# Laser_Tag_Dip_New.net
KiCad netlist of a schematic drawn in EAGLE
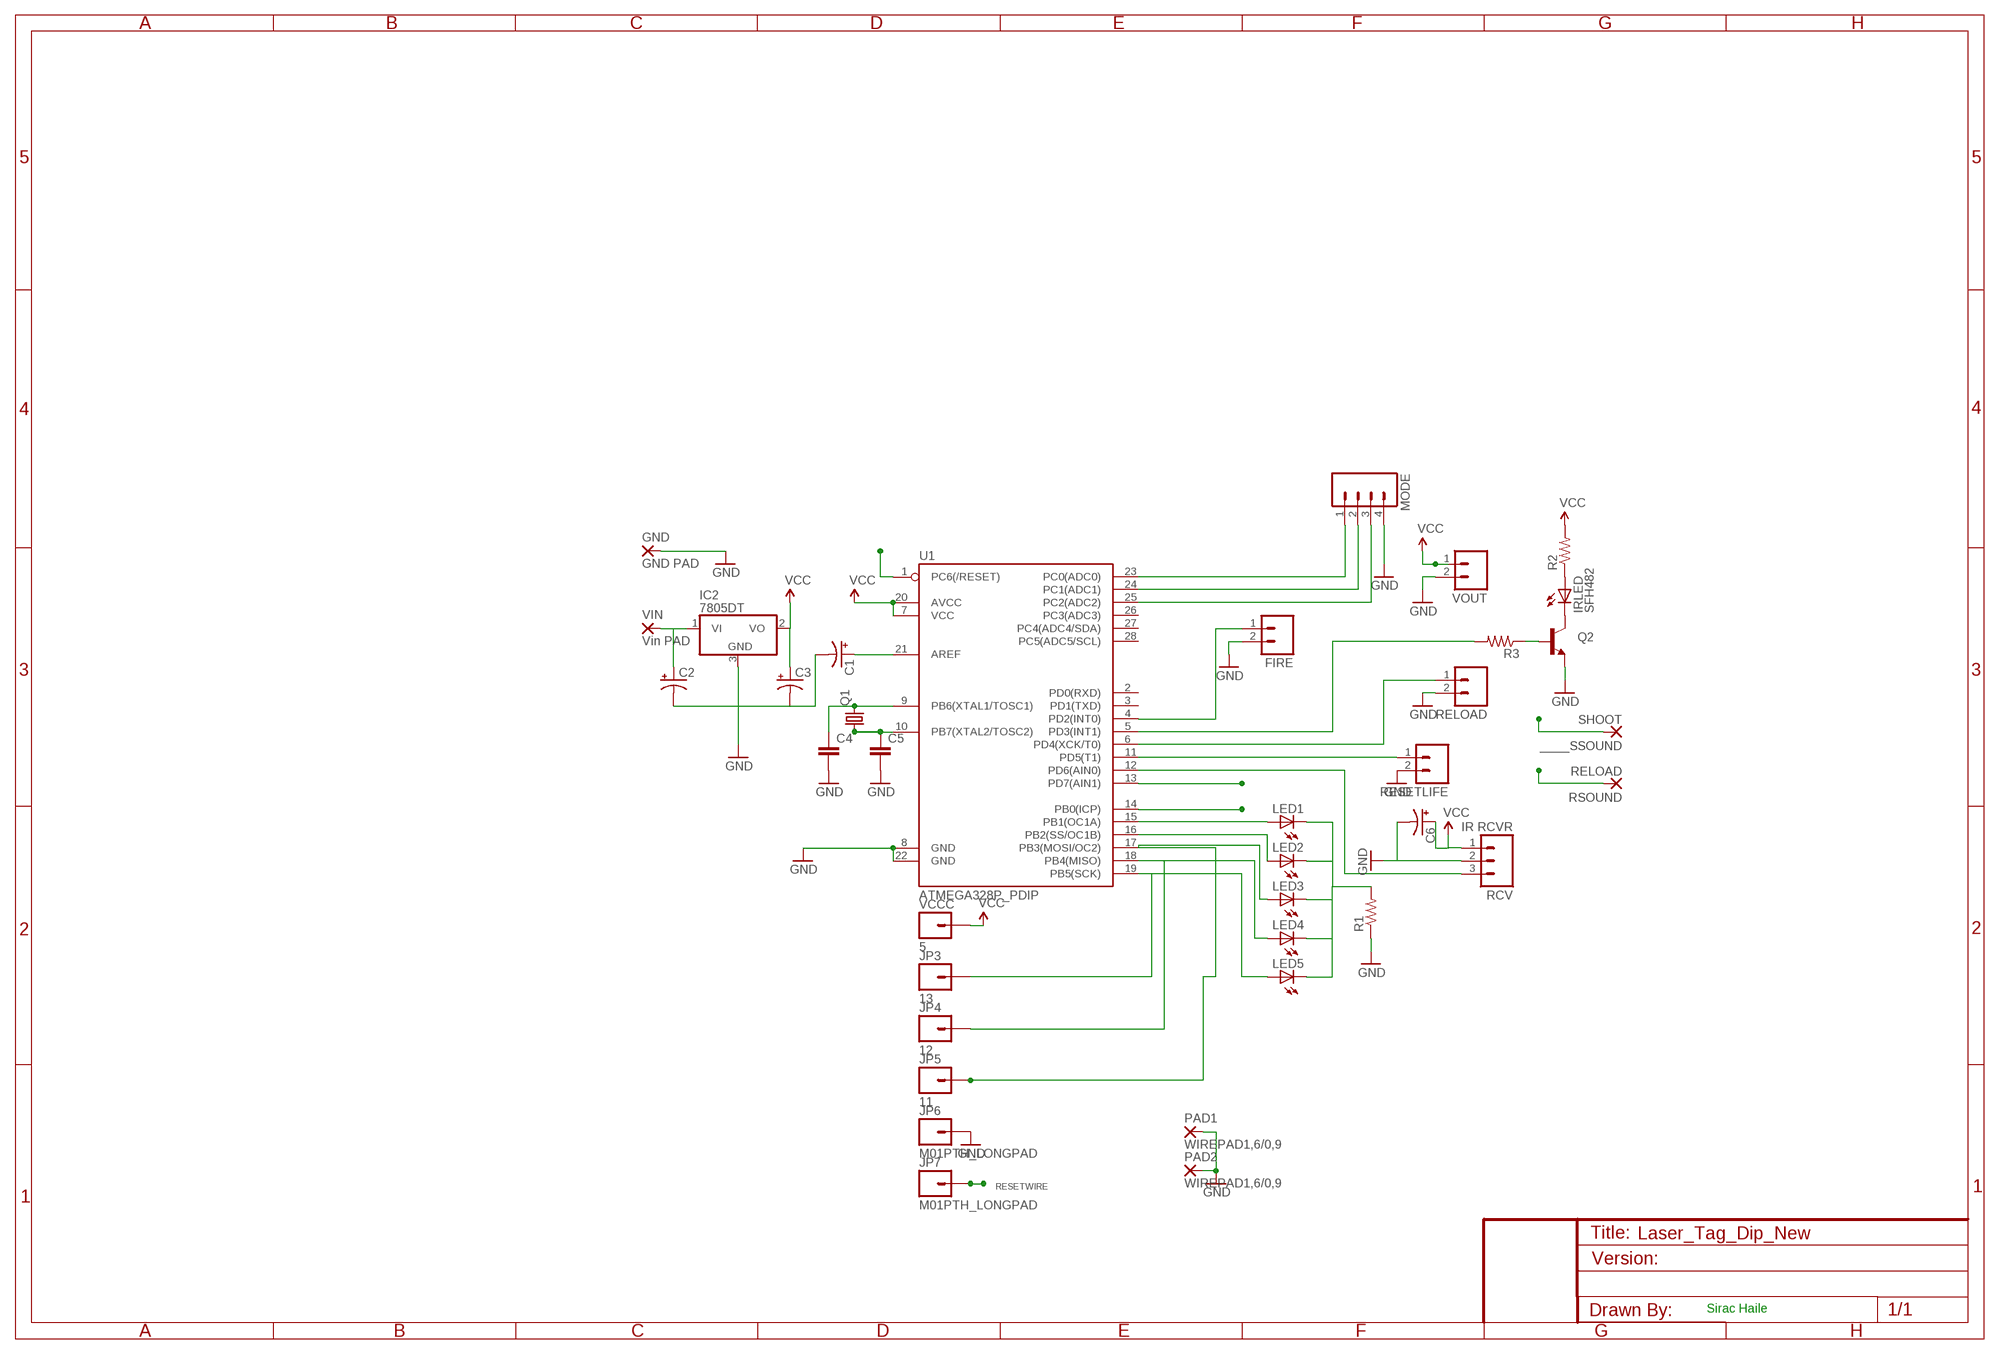
[diagram p0: schematic, sheet 1]

(export (version "E")
  (design (tool "Eeschema 10.0.6"))
  (components
    (comp (ref "C1")
      (value "CAP_POLPTH1")
      (footprint "eagle-import:CPOL-RADIAL-100UF-25V")
      (libsource (lib "eagle-import") (part "CAP_POLPTH1"))
    )
    (comp (ref "C2")
      (value "CAP_POLPTH1")
      (footprint "eagle-import:CPOL-RADIAL-100UF-25V")
      (libsource (lib "eagle-import") (part "CAP_POLPTH1"))
    )
    (comp (ref "C3")
      (value "CAP_POLPTH1")
      (footprint "eagle-import:CPOL-RADIAL-100UF-25V")
      (libsource (lib "eagle-import") (part "CAP_POLPTH1"))
    )
    (comp (ref "C4")
      (value "CAPEZ")
      (footprint "eagle-import:CAP-PTH-SMALLEZ")
      (libsource (lib "eagle-import") (part "CAPEZ"))
    )
    (comp (ref "C5")
      (value "CAPEZ")
      (footprint "eagle-import:CAP-PTH-SMALLEZ")
      (libsource (lib "eagle-import") (part "CAPEZ"))
    )
    (comp (ref "C6")
      (value "CAP_POLPTH1")
      (footprint "eagle-import:CPOL-RADIAL-100UF-25V")
      (libsource (lib "eagle-import") (part "CAP_POLPTH1"))
    )
    (comp (ref "FIRE")
      (value "M02LOCK_LONGPADS")
      (footprint "eagle-import:1X02_LOCK_LONGPADS")
      (libsource (lib "eagle-import") (part "M02LOCK_LONGPADS"))
    )
    (comp (ref "GND")
      (value "GND PAD")
      (footprint "eagle-import:2,54_1,1")
      (libsource (lib "eagle-import") (part "WIREPAD2,54/1,1"))
    )
    (comp (ref "IC2")
      (value "7805DT")
      (footprint "eagle-import:TO252")
      (libsource (lib "eagle-import") (part "78DT05"))
    )
    (comp (ref "IRLED")
      (value "SFH482")
      (footprint "eagle-import:SFH482")
      (libsource (lib "eagle-import") (part "SFH482"))
    )
    (comp (ref "JP3")
      (value "13")
      (footprint "eagle-import:1X01_LONGPAD")
      (libsource (lib "eagle-import") (part "M01PTH_LONGPAD"))
    )
    (comp (ref "JP4")
      (value "12")
      (footprint "eagle-import:1X01_LONGPAD")
      (libsource (lib "eagle-import") (part "M01PTH_LONGPAD"))
    )
    (comp (ref "JP5")
      (value "11")
      (footprint "eagle-import:1X01_LONGPAD")
      (libsource (lib "eagle-import") (part "M01PTH_LONGPAD"))
    )
    (comp (ref "JP6")
      (value "M01PTH_LONGPAD")
      (footprint "eagle-import:1X01_LONGPAD")
      (libsource (lib "eagle-import") (part "M01PTH_LONGPAD"))
    )
    (comp (ref "JP7")
      (value "M01PTH_LONGPAD")
      (footprint "eagle-import:1X01_LONGPAD")
      (libsource (lib "eagle-import") (part "M01PTH_LONGPAD"))
    )
    (comp (ref "LED1")
      (value "LED5MM")
      (footprint "eagle-import:LED5MM")
      (libsource (lib "eagle-import") (part "LED5MM"))
    )
    (comp (ref "LED2")
      (value "LED5MM")
      (footprint "eagle-import:LED5MM")
      (libsource (lib "eagle-import") (part "LED5MM"))
    )
    (comp (ref "LED3")
      (value "LED5MM")
      (footprint "eagle-import:LED5MM")
      (libsource (lib "eagle-import") (part "LED5MM"))
    )
    (comp (ref "LED4")
      (value "LED5MM")
      (footprint "eagle-import:LED5MM")
      (libsource (lib "eagle-import") (part "LED5MM"))
    )
    (comp (ref "LED5")
      (value "LED5MM")
      (footprint "eagle-import:LED5MM")
      (libsource (lib "eagle-import") (part "LED5MM"))
    )
    (comp (ref "MODE")
      (value "M04LONGPADS")
      (footprint "eagle-import:1X04_LONGPADS")
      (libsource (lib "eagle-import") (part "M04LONGPADS"))
    )
    (comp (ref "PAD1")
      (value "WIREPAD1,6/0,9")
      (footprint "eagle-import:1,6_0,9")
      (libsource (lib "eagle-import") (part "WIREPAD1,6/0,9"))
    )
    (comp (ref "PAD2")
      (value "WIREPAD1,6/0,9")
      (footprint "eagle-import:1,6_0,9")
      (libsource (lib "eagle-import") (part "WIREPAD1,6/0,9"))
    )
    (comp (ref "Q1")
      (value "CRYSTALHC49S")
      (footprint "eagle-import:HC49_S")
      (fields (field (name "OC_FARNELL") "1667008"))
      (libsource (lib "eagle-import") (part "CRYSTALHC49S"))
    )
    (comp (ref "Q2")
      (value "TRANSISTOR_NPNTO-92-AMMO")
      (footprint "eagle-import:TO-92-AMMO")
      (libsource (lib "eagle-import") (part "TRANSISTOR_NPNTO-92-AMMO"))
    )
    (comp (ref "R1")
      (value "RESISTORKIT")
      (footprint "eagle-import:AXIAL-0.3-KIT")
      (libsource (lib "eagle-import") (part "SparkFun-Resistors_RESISTORKIT"))
    )
    (comp (ref "R2")
      (value "RESISTORKIT")
      (footprint "eagle-import:AXIAL-0.3-KIT")
      (libsource (lib "eagle-import") (part "RESISTORKIT"))
    )
    (comp (ref "R3")
      (value "RESISTORKIT")
      (footprint "eagle-import:AXIAL-0.3-KIT")
      (libsource (lib "eagle-import") (part "RESISTORKIT"))
    )
    (comp (ref "RCV")
      (value "IR RCVR")
      (footprint "eagle-import:1X03")
      (libsource (lib "eagle-import") (part "M03PTH"))
    )
    (comp (ref "RELOAD")
      (value "M02LOCK_LONGPADS")
      (footprint "eagle-import:1X02_LOCK_LONGPADS")
      (libsource (lib "eagle-import") (part "M02LOCK_LONGPADS"))
    )
    (comp (ref "RESETLIFE")
      (value "M02LOCK_LONGPADS")
      (footprint "eagle-import:1X02_LOCK_LONGPADS")
      (libsource (lib "eagle-import") (part "M02LOCK_LONGPADS"))
    )
    (comp (ref "RSOUND")
      (value "RELOAD")
      (footprint "eagle-import:3,17_1,1")
      (libsource (lib "eagle-import") (part "WIREPAD3,17/1,1"))
    )
    (comp (ref "U1")
      (value "ATMEGA328P_PDIP")
      (footprint "eagle-import:DIL28-3")
      (libsource (lib "eagle-import") (part "ATMEGA328P_PDIP"))
    )
    (comp (ref "VCCC")
      (value "5")
      (footprint "eagle-import:1X01_LONGPAD")
      (libsource (lib "eagle-import") (part "M01PTH_LONGPAD"))
    )
    (comp (ref "VIN")
      (value "Vin PAD")
      (footprint "eagle-import:2,54_1,1")
      (libsource (lib "eagle-import") (part "WIREPAD2,54/1,1"))
    )
    (comp (ref "VOUT")
      (value "M02PTH3")
      (footprint "eagle-import:1X02_LONGPADS")
      (libsource (lib "eagle-import") (part "M02PTH3"))
    )
    (comp (ref "____SSOUND")
      (value "SHOOT")
      (footprint "eagle-import:3,17_1,1")
      (libsource (lib "eagle-import") (part "WIREPAD3,17/1,1"))
    )
  )
  (nets
    (net (code "1") (name "/RELOADSOUND") (class "Default")
      (node (ref "RSOUND") (pin "1") (pinfunction "P_1") (pintype "passive"))
      (node (ref "U1") (pin "14") (pinfunction "PB0(ICP)_14") (pintype "bidirectional"))
    )
    (net (code "2") (name "/RESETWIRE") (class "Default")
      (node (ref "JP7") (pin "1") (pinfunction "1_1") (pintype "passive"))
    )
    (net (code "3") (name "/SHOOTSOUND") (class "Default")
      (node (ref "U1") (pin "13") (pinfunction "PD7(AIN1)_13") (pintype "bidirectional"))
      (node (ref "____SSOUND") (pin "1") (pinfunction "P_1") (pintype "passive"))
    )
    (net (code "4") (name "GND") (class "Default")
      (node (ref "C1") (pin "2") (pinfunction "-_2") (pintype "passive"))
      (node (ref "C2") (pin "2") (pinfunction "-_2") (pintype "passive"))
      (node (ref "C3") (pin "2") (pinfunction "-_2") (pintype "passive"))
      (node (ref "C4") (pin "2") (pinfunction "2_2") (pintype "passive"))
      (node (ref "C5") (pin "2") (pinfunction "2_2") (pintype "passive"))
      (node (ref "C6") (pin "2") (pinfunction "-_2") (pintype "passive"))
      (node (ref "FIRE") (pin "2") (pinfunction "2_2") (pintype "passive"))
      (node (ref "GND") (pin "1") (pinfunction "P_1") (pintype "passive"))
      (node (ref "IC2") (pin "3") (pinfunction "GND_3") (pintype "passive"))
      (node (ref "JP6") (pin "1") (pinfunction "1_1") (pintype "passive"))
      (node (ref "MODE") (pin "4") (pinfunction "4_4") (pintype "passive"))
      (node (ref "PAD1") (pin "1") (pinfunction "P_1") (pintype "passive"))
      (node (ref "PAD2") (pin "1") (pinfunction "P_1") (pintype "passive"))
      (node (ref "Q2") (pin "1") (pinfunction "E_1") (pintype "passive"))
      (node (ref "R1") (pin "P$1") (pinfunction "1_P$1") (pintype "passive"))
      (node (ref "RCV") (pin "2") (pinfunction "2_2") (pintype "passive"))
      (node (ref "RELOAD") (pin "2") (pinfunction "2_2") (pintype "passive"))
      (node (ref "RESETLIFE") (pin "2") (pinfunction "2_2") (pintype "passive"))
      (node (ref "U1") (pin "22") (pinfunction "GND_22") (pintype "bidirectional"))
      (node (ref "U1") (pin "8") (pinfunction "GND_8") (pintype "bidirectional"))
      (node (ref "VOUT") (pin "2") (pinfunction "2_2") (pintype "passive"))
    )
    (net (code "5") (name "Net-(C1-+)") (class "Default")
      (node (ref "C1") (pin "1") (pinfunction "+_1") (pintype "passive"))
      (node (ref "U1") (pin "21") (pinfunction "AREF_21") (pintype "bidirectional"))
    )
    (net (code "6") (name "Net-(C2-+)") (class "Default")
      (node (ref "C2") (pin "1") (pinfunction "+_1") (pintype "passive"))
      (node (ref "IC2") (pin "1") (pinfunction "VI_1") (pintype "input"))
      (node (ref "VIN") (pin "1") (pinfunction "P_1") (pintype "passive"))
    )
    (net (code "7") (name "Net-(IRLED-C)") (class "Default")
      (node (ref "IRLED") (pin "K") (pinfunction "C_K") (pintype "passive"))
      (node (ref "Q2") (pin "3") (pinfunction "C_3") (pintype "passive"))
    )
    (net (code "8") (name "Net-(LED1-C)") (class "Default")
      (node (ref "LED1") (pin "K") (pinfunction "C_K") (pintype "passive"))
      (node (ref "LED2") (pin "K") (pinfunction "C_K") (pintype "passive"))
      (node (ref "LED3") (pin "K") (pinfunction "C_K") (pintype "passive"))
      (node (ref "LED4") (pin "K") (pinfunction "C_K") (pintype "passive"))
      (node (ref "LED5") (pin "K") (pinfunction "C_K") (pintype "passive"))
      (node (ref "R1") (pin "P$2") (pinfunction "2_P$2") (pintype "passive"))
    )
    (net (code "9") (name "Net-(Q2-B)") (class "Default")
      (node (ref "Q2") (pin "2") (pinfunction "B_2") (pintype "passive"))
      (node (ref "R3") (pin "P$1") (pinfunction "1_P$1") (pintype "passive"))
    )
    (net (code "10") (name "Net-(R2-1)") (class "Default")
      (node (ref "IRLED") (pin "A") (pinfunction "A_A") (pintype "passive"))
      (node (ref "R2") (pin "P$1") (pinfunction "1_P$1") (pintype "passive"))
    )
    (net (code "11") (name "Net-(R3-2)") (class "Default")
      (node (ref "R3") (pin "P$2") (pinfunction "2_P$2") (pintype "passive"))
      (node (ref "U1") (pin "5") (pinfunction "PD3(INT1)_5") (pintype "bidirectional"))
    )
    (net (code "12") (name "Net-(U1-PB1(OC1A))") (class "Default")
      (node (ref "LED1") (pin "A") (pinfunction "A_A") (pintype "passive"))
      (node (ref "U1") (pin "15") (pinfunction "PB1(OC1A)_15") (pintype "bidirectional"))
    )
    (net (code "13") (name "Net-(U1-PB2(SS{slash}OC1B))") (class "Default")
      (node (ref "LED2") (pin "A") (pinfunction "A_A") (pintype "passive"))
      (node (ref "U1") (pin "16") (pinfunction "PB2(SS/OC1B)_16") (pintype "bidirectional"))
    )
    (net (code "14") (name "Net-(U1-PB3(MOSI{slash}OC2))") (class "Default")
      (node (ref "JP5") (pin "1") (pinfunction "1_1") (pintype "passive"))
      (node (ref "LED3") (pin "A") (pinfunction "A_A") (pintype "passive"))
      (node (ref "U1") (pin "17") (pinfunction "PB3(MOSI/OC2)_17") (pintype "bidirectional"))
    )
    (net (code "15") (name "Net-(U1-PB4(MISO))") (class "Default")
      (node (ref "JP4") (pin "1") (pinfunction "1_1") (pintype "passive"))
      (node (ref "LED4") (pin "A") (pinfunction "A_A") (pintype "passive"))
      (node (ref "U1") (pin "18") (pinfunction "PB4(MISO)_18") (pintype "bidirectional"))
    )
    (net (code "16") (name "Net-(U1-PB5(SCK))") (class "Default")
      (node (ref "JP3") (pin "1") (pinfunction "1_1") (pintype "passive"))
      (node (ref "LED5") (pin "A") (pinfunction "A_A") (pintype "passive"))
      (node (ref "U1") (pin "19") (pinfunction "PB5(SCK)_19") (pintype "bidirectional"))
    )
    (net (code "17") (name "Net-(U1-PB6(XTAL1{slash}TOSC1))") (class "Default")
      (node (ref "C4") (pin "1") (pinfunction "1_1") (pintype "passive"))
      (node (ref "Q1") (pin "2") (pinfunction "2_2") (pintype "passive"))
      (node (ref "U1") (pin "9") (pinfunction "PB6(XTAL1/TOSC1)_9") (pintype "bidirectional"))
    )
    (net (code "18") (name "Net-(U1-PB7(XTAL2{slash}TOSC2))") (class "Default")
      (node (ref "C5") (pin "1") (pinfunction "1_1") (pintype "passive"))
      (node (ref "Q1") (pin "1") (pinfunction "1_1") (pintype "passive"))
      (node (ref "U1") (pin "10") (pinfunction "PB7(XTAL2/TOSC2)_10") (pintype "bidirectional"))
    )
    (net (code "19") (name "Net-(U1-PC0(ADC0))") (class "Default")
      (node (ref "MODE") (pin "1") (pinfunction "1_1") (pintype "passive"))
      (node (ref "U1") (pin "23") (pinfunction "PC0(ADC0)_23") (pintype "bidirectional"))
    )
    (net (code "20") (name "Net-(U1-PC1(ADC1))") (class "Default")
      (node (ref "MODE") (pin "2") (pinfunction "2_2") (pintype "passive"))
      (node (ref "U1") (pin "24") (pinfunction "PC1(ADC1)_24") (pintype "bidirectional"))
    )
    (net (code "21") (name "Net-(U1-PC2(ADC2))") (class "Default")
      (node (ref "MODE") (pin "3") (pinfunction "3_3") (pintype "passive"))
      (node (ref "U1") (pin "25") (pinfunction "PC2(ADC2)_25") (pintype "bidirectional"))
    )
    (net (code "22") (name "Net-(U1-PD2(INT0))") (class "Default")
      (node (ref "FIRE") (pin "1") (pinfunction "1_1") (pintype "passive"))
      (node (ref "U1") (pin "4") (pinfunction "PD2(INT0)_4") (pintype "bidirectional"))
    )
    (net (code "23") (name "Net-(U1-PD4(XCK{slash}T0))") (class "Default")
      (node (ref "RELOAD") (pin "1") (pinfunction "1_1") (pintype "passive"))
      (node (ref "U1") (pin "6") (pinfunction "PD4(XCK/T0)_6") (pintype "bidirectional"))
    )
    (net (code "24") (name "Net-(U1-PD5(T1))") (class "Default")
      (node (ref "RESETLIFE") (pin "1") (pinfunction "1_1") (pintype "passive"))
      (node (ref "U1") (pin "11") (pinfunction "PD5(T1)_11") (pintype "bidirectional"))
    )
    (net (code "25") (name "Net-(U1-PD6(AIN0))") (class "Default")
      (node (ref "RCV") (pin "3") (pinfunction "3_3") (pintype "passive"))
      (node (ref "U1") (pin "12") (pinfunction "PD6(AIN0)_12") (pintype "bidirectional"))
    )
    (net (code "26") (name "VCC") (class "Default")
      (node (ref "C3") (pin "1") (pinfunction "+_1") (pintype "passive"))
      (node (ref "C6") (pin "1") (pinfunction "+_1") (pintype "passive"))
      (node (ref "IC2") (pin "2") (pinfunction "VO_2") (pintype "passive"))
      (node (ref "R2") (pin "P$2") (pinfunction "2_P$2") (pintype "passive"))
      (node (ref "RCV") (pin "1") (pinfunction "1_1") (pintype "passive"))
      (node (ref "U1") (pin "20") (pinfunction "AVCC_20") (pintype "bidirectional"))
      (node (ref "U1") (pin "7") (pinfunction "VCC_7") (pintype "bidirectional"))
      (node (ref "VCCC") (pin "1") (pinfunction "1_1") (pintype "passive"))
      (node (ref "VOUT") (pin "1") (pinfunction "1_1") (pintype "passive"))
    )
    (net (code "27") (name "unconnected-(U1-PC3(ADC3)-Pad26)") (class "Default")
      (node (ref "U1") (pin "26") (pinfunction "PC3(ADC3)_26") (pintype "bidirectional"))
    )
    (net (code "28") (name "unconnected-(U1-PC4(ADC4{slash}SDA)-Pad27)") (class "Default")
      (node (ref "U1") (pin "27") (pinfunction "PC4(ADC4/SDA)_27") (pintype "bidirectional"))
    )
    (net (code "29") (name "unconnected-(U1-PC5(ADC5{slash}SCL)-Pad28)") (class "Default")
      (node (ref "U1") (pin "28") (pinfunction "PC5(ADC5/SCL)_28") (pintype "bidirectional"))
    )
    (net (code "30") (name "unconnected-(U1-PC6({slash}RESET)-Pad1)") (class "Default")
      (node (ref "U1") (pin "1") (pinfunction "PC6(/RESET)_1") (pintype "bidirectional"))
    )
    (net (code "31") (name "unconnected-(U1-PD0(RXD)-Pad2)") (class "Default")
      (node (ref "U1") (pin "2") (pinfunction "PD0(RXD)_2") (pintype "bidirectional"))
    )
    (net (code "32") (name "unconnected-(U1-PD1(TXD)-Pad3)") (class "Default")
      (node (ref "U1") (pin "3") (pinfunction "PD1(TXD)_3") (pintype "bidirectional"))
    )
  )
)
